# Power.net
KiCad netlist of a schematic drawn in Altium Designer
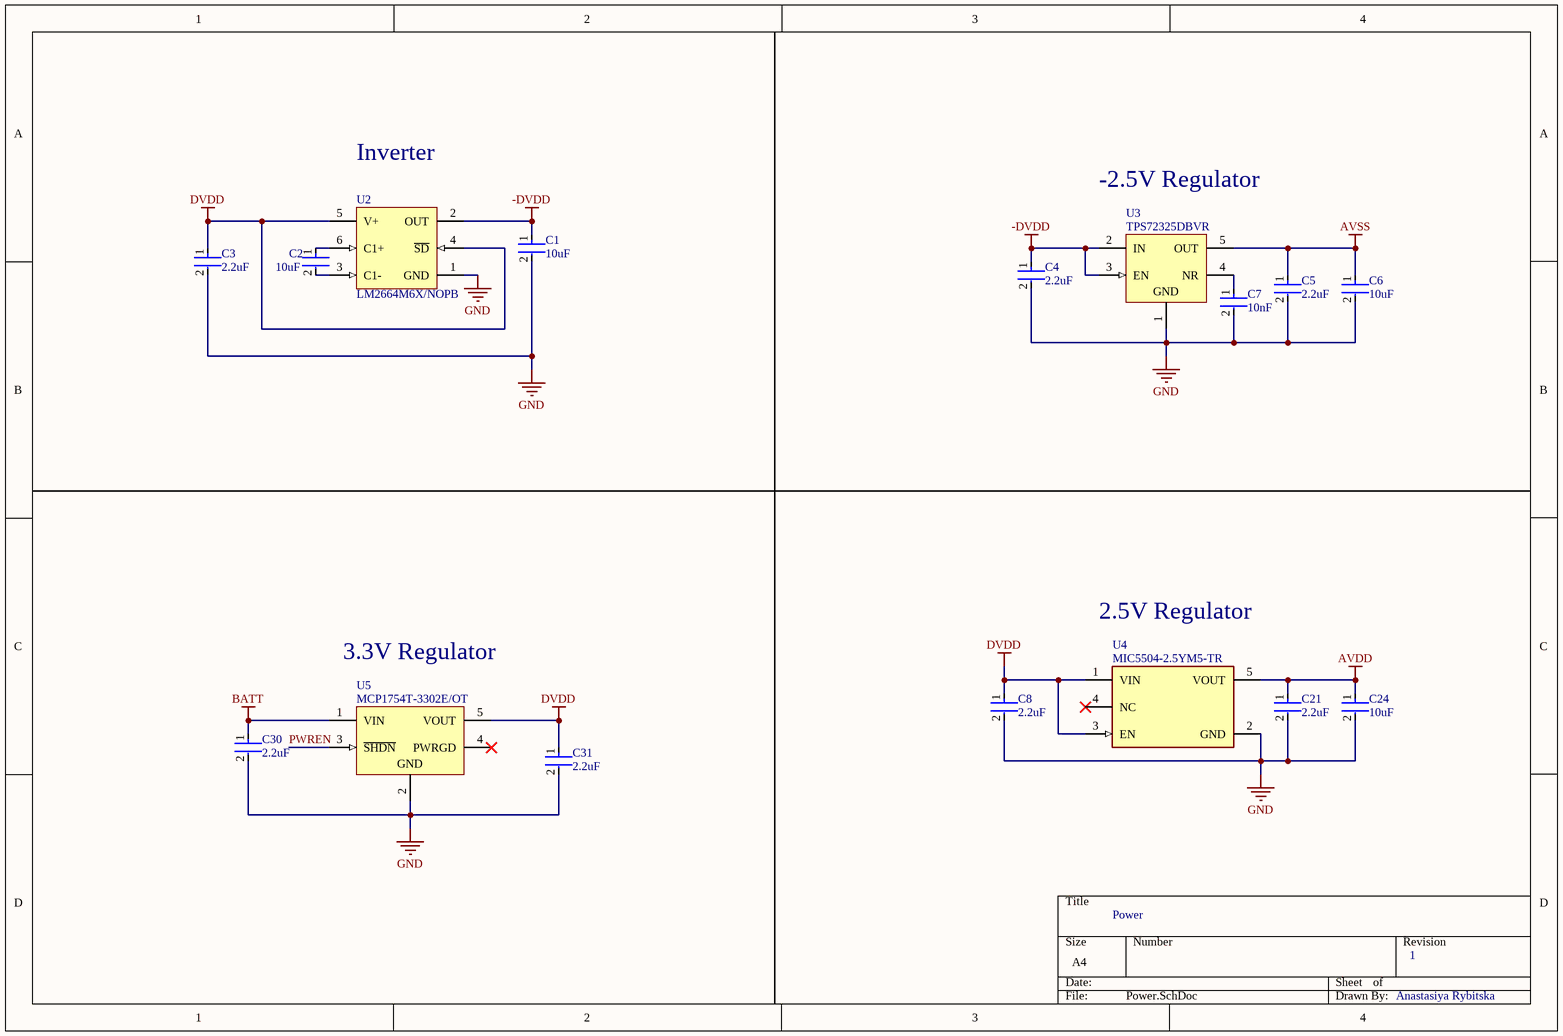
[diagram p0: Power.SchDoc]

(export (version "E")
  (design (tool "Eeschema 10.0.6"))
  (components
    (comp (ref "C1")
      (value "CL10A106MQ8NNNC")
      (footprint "FP-CL10-IPC_C")
      (description "Cap Ceramic 10uF 6.3V X5R ±20% Pad SMD 0603 +85°C T/R")
      (fields
        (field (name "CAPACITANCE") "10uF")
        (field (name "VOLTAGE") "6.3V")
        (field (name "TOLERANCE") "20%")
      )
      (libsource (lib "Altium Content Vault") (part "b4654b650e69147ec39a6b967a45e02"))
    )
    (comp (ref "C2")
      (value "CL10A106MQ8NNNC")
      (footprint "FP-CL10-IPC_C")
      (description "Cap Ceramic 10uF 6.3V X5R ±20% Pad SMD 0603 +85°C T/R")
      (fields
        (field (name "CAPACITANCE") "10uF")
        (field (name "VOLTAGE") "6.3V")
        (field (name "TOLERANCE") "20%")
      )
      (libsource (lib "Altium Content Vault") (part "b4654b650e69147ec39a6b967a45e02"))
    )
    (comp (ref "C3")
      (value "CL10A225KO8NNNC")
      (footprint "FP-CL10-IPC_A")
      (description "Cap Ceramic 2.2uF 16V X5R ±10% Pad SMD 0603 +85°C T/R")
      (fields
        (field (name "CAPACITANCE") "2.2uF")
        (field (name "TOLERANCE") "10%")
        (field (name "VOLTAGE") "16V")
      )
      (libsource (lib "Altium Content Vault") (part "b4654b650e69147ec39a6b967a45e02"))
    )
    (comp (ref "C4")
      (value "CL10A225KO8NNNC")
      (footprint "FP-CL10-IPC_A")
      (description "Cap Ceramic 2.2uF 16V X5R ±10% Pad SMD 0603 +85°C T/R")
      (fields
        (field (name "CAPACITANCE") "2.2uF")
        (field (name "TOLERANCE") "10%")
        (field (name "VOLTAGE") "16V")
      )
      (libsource (lib "Altium Content Vault") (part "b4654b650e69147ec39a6b967a45e02"))
    )
    (comp (ref "C5")
      (value "CL10A225KO8NNNC")
      (footprint "FP-CL10-IPC_A")
      (description "Cap Ceramic 2.2uF 16V X5R ±10% Pad SMD 0603 +85°C T/R")
      (fields
        (field (name "CAPACITANCE") "2.2uF")
        (field (name "TOLERANCE") "10%")
        (field (name "VOLTAGE") "16V")
      )
      (libsource (lib "Altium Content Vault") (part "b4654b650e69147ec39a6b967a45e02"))
    )
    (comp (ref "C6")
      (value "CL10A106MQ8NNNC")
      (footprint "FP-CL10-IPC_C")
      (description "Cap Ceramic 10uF 6.3V X5R ±20% Pad SMD 0603 +85°C T/R")
      (fields
        (field (name "CAPACITANCE") "10uF")
        (field (name "VOLTAGE") "6.3V")
        (field (name "TOLERANCE") "20%")
      )
      (libsource (lib "Altium Content Vault") (part "b4654b650e69147ec39a6b967a45e02"))
    )
    (comp (ref "C7")
      (value "10nF")
      (footprint "FP-CC0603-DA-MFG")
      (description "CAP CER 10000PF 50V X7R 0603")
      (fields (field (name "TOLERANCE") "0.1") (field (name "MANUFACTURER PART NUMBER") "CC0603KRX7R9BB103"))
      (libsource (lib "Altium Content Vault") (part "11868f565c42a9108669ba33697ecf6"))
    )
    (comp (ref "C8")
      (value "CL10A225KO8NNNC")
      (footprint "FP-CL10-IPC_A")
      (description "Cap Ceramic 2.2uF 16V X5R ±10% Pad SMD 0603 +85°C T/R")
      (fields
        (field (name "CAPACITANCE") "2.2uF")
        (field (name "TOLERANCE") "10%")
        (field (name "VOLTAGE") "16V")
      )
      (libsource (lib "Altium Content Vault") (part "b4654b650e69147ec39a6b967a45e02"))
    )
    (comp (ref "C21")
      (value "CL10A225KO8NNNC")
      (footprint "FP-CL10-IPC_A")
      (description "Cap Ceramic 2.2uF 16V X5R ±10% Pad SMD 0603 +85°C T/R")
      (fields
        (field (name "CAPACITANCE") "2.2uF")
        (field (name "TOLERANCE") "10%")
        (field (name "VOLTAGE") "16V")
      )
      (libsource (lib "Altium Content Vault") (part "b4654b650e69147ec39a6b967a45e02"))
    )
    (comp (ref "C24")
      (value "CL10A106MQ8NNNC")
      (footprint "FP-CL10-IPC_C")
      (description "Cap Ceramic 10uF 6.3V X5R ±20% Pad SMD 0603 +85°C T/R")
      (fields
        (field (name "CAPACITANCE") "10uF")
        (field (name "VOLTAGE") "6.3V")
        (field (name "TOLERANCE") "20%")
      )
      (libsource (lib "Altium Content Vault") (part "b4654b650e69147ec39a6b967a45e02"))
    )
    (comp (ref "C30")
      (value "CL10A225KO8NNNC")
      (footprint "FP-CL10-IPC_A")
      (description "Cap Ceramic 2.2uF 16V X5R ±10% Pad SMD 0603 +85°C T/R")
      (fields
        (field (name "CAPACITANCE") "2.2uF")
        (field (name "TOLERANCE") "10%")
        (field (name "VOLTAGE") "16V")
      )
      (libsource (lib "Altium Content Vault") (part "b4654b650e69147ec39a6b967a45e02"))
    )
    (comp (ref "C31")
      (value "CL10A225KO8NNNC")
      (footprint "FP-CL10-IPC_A")
      (description "Cap Ceramic 2.2uF 16V X5R ±10% Pad SMD 0603 +85°C T/R")
      (fields
        (field (name "CAPACITANCE") "2.2uF")
        (field (name "TOLERANCE") "10%")
        (field (name "VOLTAGE") "16V")
      )
      (libsource (lib "Altium Content Vault") (part "b4654b650e69147ec39a6b967a45e02"))
    )
    (comp (ref "U2")
      (value "LM2664M6X/NOPB")
      (footprint "DBV0006A_M")
      (description "Switched Capacitor Voltage Converter, 6-pin SOT-23, Pb-Free")
      (fields (field (name "MANUFACTURER") "Texas Instruments"))
      (libsource (lib "Altium Content Vault") (part "PM-CHP-LM2664M6-6"))
    )
    (comp (ref "U3")
      (value "TPS72325DBVR")
      (footprint "DBV0005A_N")
      (fields (field (name "MANUFACTURER") "Texas Instruments"))
      (libsource (lib "Altium Content Vault") (part "TI-TPS72325-DBV5"))
    )
    (comp (ref "U4")
      (value "MIC5504-2.5YM5-TR")
      (footprint "FP-SOT23-5LD-PL-1-IPC_C")
      (description "IC REG LINEAR 2.5V 300MA SOT23-5")
      (libsource (lib "Altium Content Vault") (part "138c81f6bb701432dd5e458166d856b"))
    )
    (comp (ref "U5")
      (value "MCP1754T-3302E/OT")
      (footprint "MCHP-SOT-23-OT5_L")
      (description "150 mA, 16 V, High Performance LDO, -40 to 125 degC, 5-pin SOT-23 (OT5), Tape and Reel")
      (fields (field (name "MANUFACTURER") "Microchip"))
      (libsource (lib "Altium Content Vault") (part "MCHP-MCP1754-SOT-23-5"))
    )
  )
  (nets
    (net (code "1") (name "-DVDD") (class "Default")
      (node (ref "C1") (pin "1") (pinfunction "1_1") (pintype "passive"))
      (node (ref "C4") (pin "1") (pinfunction "1_1") (pintype "passive"))
      (node (ref "U2") (pin "2") (pinfunction "OUT_2") (pintype "power_in"))
      (node (ref "U3") (pin "2") (pinfunction "IN_2") (pintype "power_in"))
      (node (ref "U3") (pin "3") (pinfunction "EN_3") (pintype "input"))
    )
    (net (code "2") (name "/PWREN") (class "Default")
      (node (ref "U5") (pin "3") (pinfunction "~{SHDN}_3") (pintype "input"))
    )
    (net (code "3") (name "AVDD") (class "Default")
      (node (ref "C21") (pin "1") (pinfunction "1_1") (pintype "passive"))
      (node (ref "C24") (pin "1") (pinfunction "1_1") (pintype "passive"))
      (node (ref "U4") (pin "5") (pinfunction "VOUT_5") (pintype "power_in"))
    )
    (net (code "4") (name "AVSS") (class "Default")
      (node (ref "C5") (pin "1") (pinfunction "1_1") (pintype "passive"))
      (node (ref "C6") (pin "1") (pinfunction "1_1") (pintype "passive"))
      (node (ref "U3") (pin "5") (pinfunction "OUT_5") (pintype "power_in"))
    )
    (net (code "5") (name "BATT") (class "Default")
      (node (ref "C30") (pin "1") (pinfunction "1_1") (pintype "passive"))
      (node (ref "U5") (pin "1") (pinfunction "VIN_1") (pintype "power_in"))
    )
    (net (code "6") (name "DVDD") (class "Default")
      (node (ref "C3") (pin "1") (pinfunction "1_1") (pintype "passive"))
      (node (ref "C31") (pin "1") (pinfunction "1_1") (pintype "passive"))
      (node (ref "C8") (pin "1") (pinfunction "1_1") (pintype "passive"))
      (node (ref "U2") (pin "4") (pinfunction "~{SD}_4") (pintype "input"))
      (node (ref "U2") (pin "5") (pinfunction "V+_5") (pintype "power_in"))
      (node (ref "U4") (pin "1") (pinfunction "VIN_1") (pintype "open_emitter"))
      (node (ref "U4") (pin "3") (pinfunction "EN_3") (pintype "input"))
      (node (ref "U5") (pin "5") (pinfunction "VOUT_5") (pintype "power_in"))
    )
    (net (code "7") (name "GND") (class "Default")
      (node (ref "C1") (pin "2") (pinfunction "2_2") (pintype "passive"))
      (node (ref "C21") (pin "2") (pinfunction "2_2") (pintype "passive"))
      (node (ref "C24") (pin "2") (pinfunction "2_2") (pintype "passive"))
      (node (ref "C3") (pin "2") (pinfunction "2_2") (pintype "passive"))
      (node (ref "C30") (pin "2") (pinfunction "2_2") (pintype "passive"))
      (node (ref "C31") (pin "2") (pinfunction "2_2") (pintype "passive"))
      (node (ref "C4") (pin "2") (pinfunction "2_2") (pintype "passive"))
      (node (ref "C5") (pin "2") (pinfunction "2_2") (pintype "passive"))
      (node (ref "C6") (pin "2") (pinfunction "2_2") (pintype "passive"))
      (node (ref "C7") (pin "2") (pinfunction "2_2") (pintype "passive"))
      (node (ref "C8") (pin "2") (pinfunction "2_2") (pintype "passive"))
      (node (ref "U2") (pin "1") (pinfunction "GND_1") (pintype "power_in"))
      (node (ref "U3") (pin "1") (pinfunction "GND_1") (pintype "power_in"))
      (node (ref "U4") (pin "2") (pinfunction "GND_2") (pintype "power_in"))
      (node (ref "U5") (pin "2") (pinfunction "GND_2") (pintype "power_in"))
    )
    (net (code "8") (name "Net-(U2-C1+)") (class "Default")
      (node (ref "C2") (pin "1") (pinfunction "1_1") (pintype "passive"))
      (node (ref "U2") (pin "6") (pinfunction "C1+_6") (pintype "input"))
    )
    (net (code "9") (name "Net-(U2-C1-)") (class "Default")
      (node (ref "C2") (pin "2") (pinfunction "2_2") (pintype "passive"))
      (node (ref "U2") (pin "3") (pinfunction "C1-_3") (pintype "input"))
    )
    (net (code "10") (name "Net-(U3-NR)") (class "Default")
      (node (ref "C7") (pin "1") (pinfunction "1_1") (pintype "passive"))
      (node (ref "U3") (pin "4") (pinfunction "NR_4") (pintype "passive"))
    )
    (net (code "11") (name "unconnected-(U4-NC-Pad4)") (class "Default")
      (node (ref "U4") (pin "4") (pinfunction "NC_4") (pintype "passive+no_connect"))
    )
    (net (code "12") (name "unconnected-(U5-PWRGD-Pad4)") (class "Default")
      (node (ref "U5") (pin "4") (pinfunction "PWRGD_4") (pintype "open_collector+no_connect"))
    )
  )
)
